# Power_3v3.net
KiCad netlist of a schematic drawn in Altium Designer
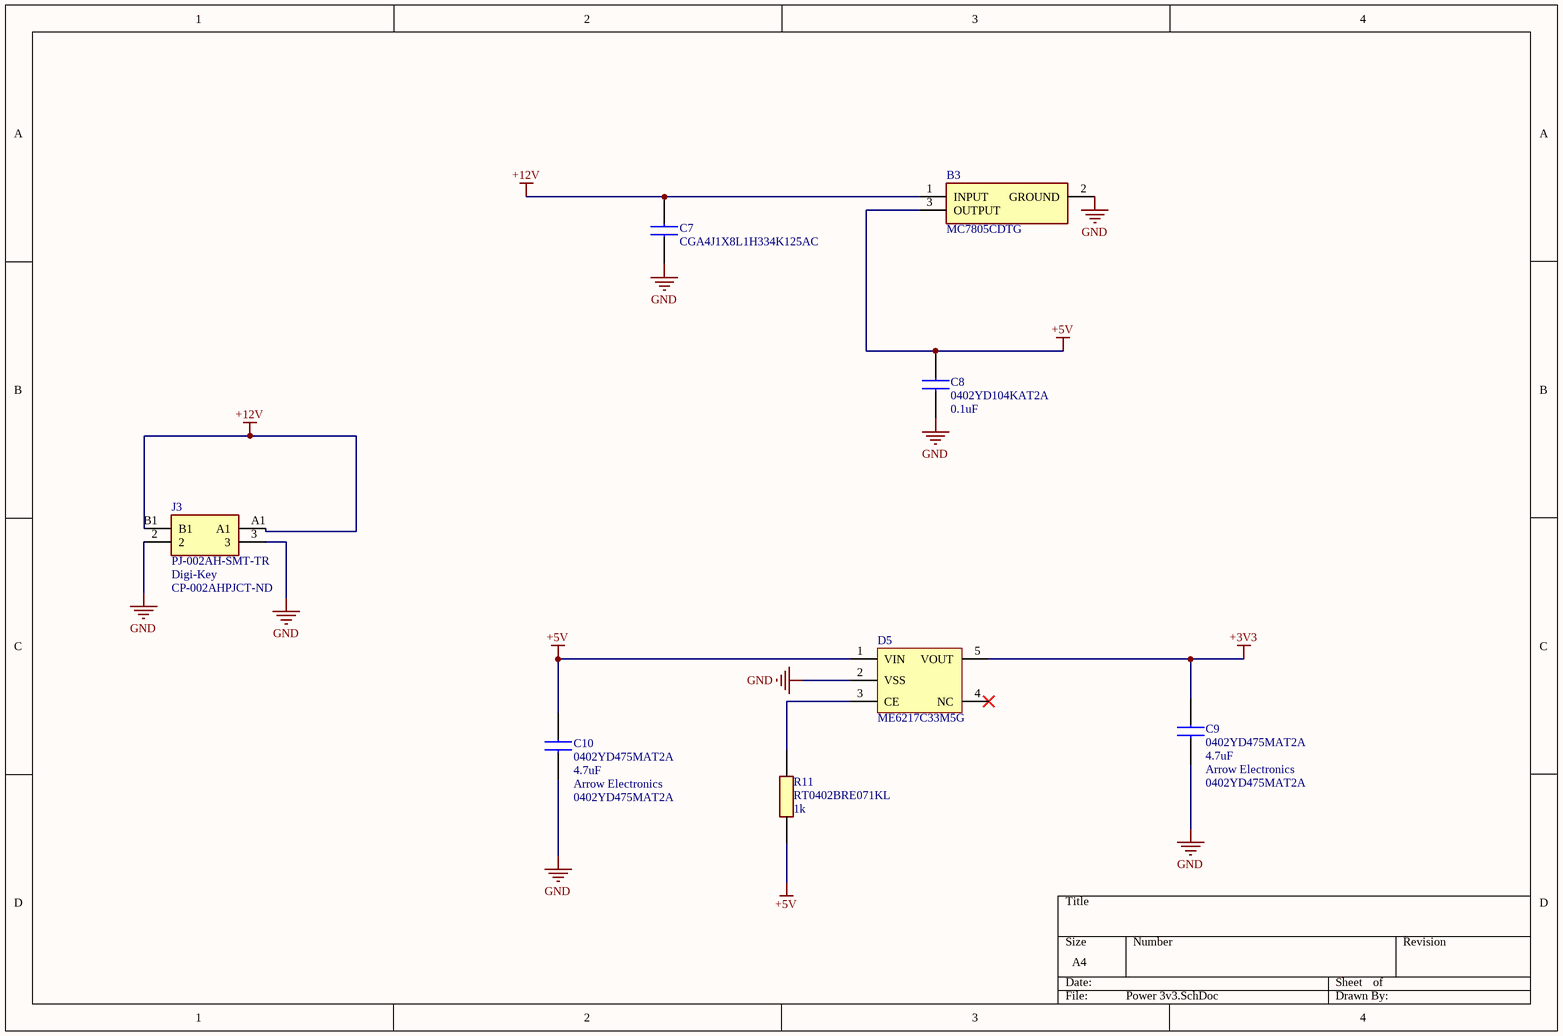
[diagram p0: Power 3v3.SchDoc]

(export (version "E")
  (design (tool "Eeschema 10.0.6"))
  (components
    (comp (ref "B3")
      (value "MC7805CDTG")
      (footprint "MC7805CDTG")
      (description "Linear Voltage Regulators 5V 1A Positive")
      (fields (field (name "MOUSER PART NUMBER") "863-MC7805CDTG"))
      (libsource (lib "SFMproject") (part "MC7805CDTG"))
    )
    (comp (ref "C7")
      (value "CGA4J1X8L1H334K125AC")
      (footprint "CAPC2012X145N")
      (description "Multilayer Ceramic Chip Capacitors, Capacitance=0.33uF, LxWxT:2x1.25x1.25mm")
      (fields (field (name "MOUSER PART NUMBER") "810-CGA4J1X8L1H334K1"))
      (libsource (lib "SFMproject") (part "CGA4J1X8L1H334K125AC"))
    )
    (comp (ref "C8")
      (value "0402YD104KAT2A")
      (footprint "CAPC1005X40N")
      (fields (field (name "MOUSER PART NUMBER") "581-0402YD104K") (field (name "ALTIUM_VALUE") "0.1uF"))
      (libsource (lib "SFMproject") (part "0402YD104KAT2A"))
    )
    (comp (ref "C9")
      (value "0402YD475MAT2A")
      (footprint "CAPC1005X40N")
      (description "Multilayer Ceramic Capacitors MLCC - SMD/SMT 16V 4.7uF 20% X5R 0402")
      (fields
        (field (name "MOUSER PART NUMBER") "581-0402YD475MAT2A")
        (field (name "ALTIUM_VALUE") "4.7uF")
        (field (name "SUPPLIER 1") "Arrow Electronics")
        (field (name "SUPPLIER PART NUMBER 1") "0402YD475MAT2A")
      )
      (libsource (lib "SFMproject") (part "0402YD475MAT2A"))
    )
    (comp (ref "C10")
      (value "0402YD475MAT2A")
      (footprint "CAPC1005X40N")
      (description "Multilayer Ceramic Capacitors MLCC - SMD/SMT 16V 4.7uF 20% X5R 0402")
      (fields
        (field (name "MOUSER PART NUMBER") "581-0402YD475MAT2A")
        (field (name "ALTIUM_VALUE") "4.7uF")
        (field (name "SUPPLIER 1") "Arrow Electronics")
        (field (name "SUPPLIER PART NUMBER 1") "0402YD475MAT2A")
      )
      (libsource (lib "SFMproject") (part "0402YD475MAT2A"))
    )
    (comp (ref "D5")
      (value "ME6217C33M5G")
      (footprint "SOT-23-5_L2.9-W1.6-P0.95-LS2.8-BR")
      (libsource (lib "SFMproject") (part "ME6217C33M5G / SOT23-5"))
    )
    (comp (ref "J3")
      (value "PJ-002AH-SMT-TR")
      (footprint "PJ002AHSMTTR")
      (description "DC Power Connectors Power Jacks")
      (fields
        (field (name "MOUSER PART NUMBER") "490-PJ-002AH-SMT-TR")
        (field (name "SUPPLIER 1") "Digi-Key")
        (field (name "SUPPLIER PART NUMBER 1") "CP-002AHPJCT-ND")
      )
      (libsource (lib "SFMproject") (part "PJ-002AH-SMT-TR"))
    )
    (comp (ref "R11")
      (value "RT0402BRE071KL")
      (footprint "RESC1005X40N")
      (description "Thin Film Resistors - SMD 1/16W 1K ohm .1% 50ppm")
      (fields (field (name "MOUSER PART NUMBER") "603-RT0402BRE071KL") (field (name "ALTIUM_VALUE") "1k"))
      (libsource (lib "SFMproject") (part "RT0402BRE071KL"))
    )
  )
  (nets
    (net (code "1") (name "+3V3") (class "Default")
      (node (ref "C9") (pin "2") (pinfunction "2_2") (pintype "passive"))
      (node (ref "D5") (pin "5") (pinfunction "VOUT_5") (pintype "passive"))
    )
    (net (code "2") (name "+5V") (class "Default")
      (node (ref "B3") (pin "3") (pinfunction "OUTPUT_3") (pintype "passive"))
      (node (ref "C10") (pin "2") (pinfunction "2_2") (pintype "passive"))
      (node (ref "C8") (pin "2") (pinfunction "2_2") (pintype "passive"))
      (node (ref "D5") (pin "1") (pinfunction "VIN_1") (pintype "passive"))
      (node (ref "R11") (pin "1") (pinfunction "1_1") (pintype "passive"))
    )
    (net (code "3") (name "+12V") (class "Default")
      (node (ref "B3") (pin "1") (pinfunction "INPUT_1") (pintype "passive"))
      (node (ref "C7") (pin "2") (pinfunction "2_2") (pintype "passive"))
      (node (ref "J3") (pin "A1") (pinfunction "A1_A1") (pintype "passive"))
      (node (ref "J3") (pin "B1") (pinfunction "B1_B1") (pintype "passive"))
    )
    (net (code "4") (name "GND") (class "Default")
      (node (ref "B3") (pin "2") (pinfunction "GROUND_2") (pintype "passive"))
      (node (ref "C10") (pin "1") (pinfunction "1_1") (pintype "passive"))
      (node (ref "C7") (pin "1") (pinfunction "1_1") (pintype "passive"))
      (node (ref "C8") (pin "1") (pinfunction "1_1") (pintype "passive"))
      (node (ref "C9") (pin "1") (pinfunction "1_1") (pintype "passive"))
      (node (ref "D5") (pin "2") (pinfunction "VSS_2") (pintype "passive"))
      (node (ref "J3") (pin "2") (pinfunction "2_2") (pintype "passive"))
      (node (ref "J3") (pin "3") (pinfunction "3_3") (pintype "passive"))
    )
    (net (code "5") (name "Net-(D5-CE)") (class "Default")
      (node (ref "D5") (pin "3") (pinfunction "CE_3") (pintype "passive"))
      (node (ref "R11") (pin "2") (pinfunction "2_2") (pintype "passive"))
    )
    (net (code "6") (name "unconnected-(D5-NC-Pad4)") (class "Default")
      (node (ref "D5") (pin "4") (pinfunction "NC_4") (pintype "passive+no_connect"))
    )
  )
)
